# BSPD.net
KiCad netlist of a schematic drawn in Altium Designer
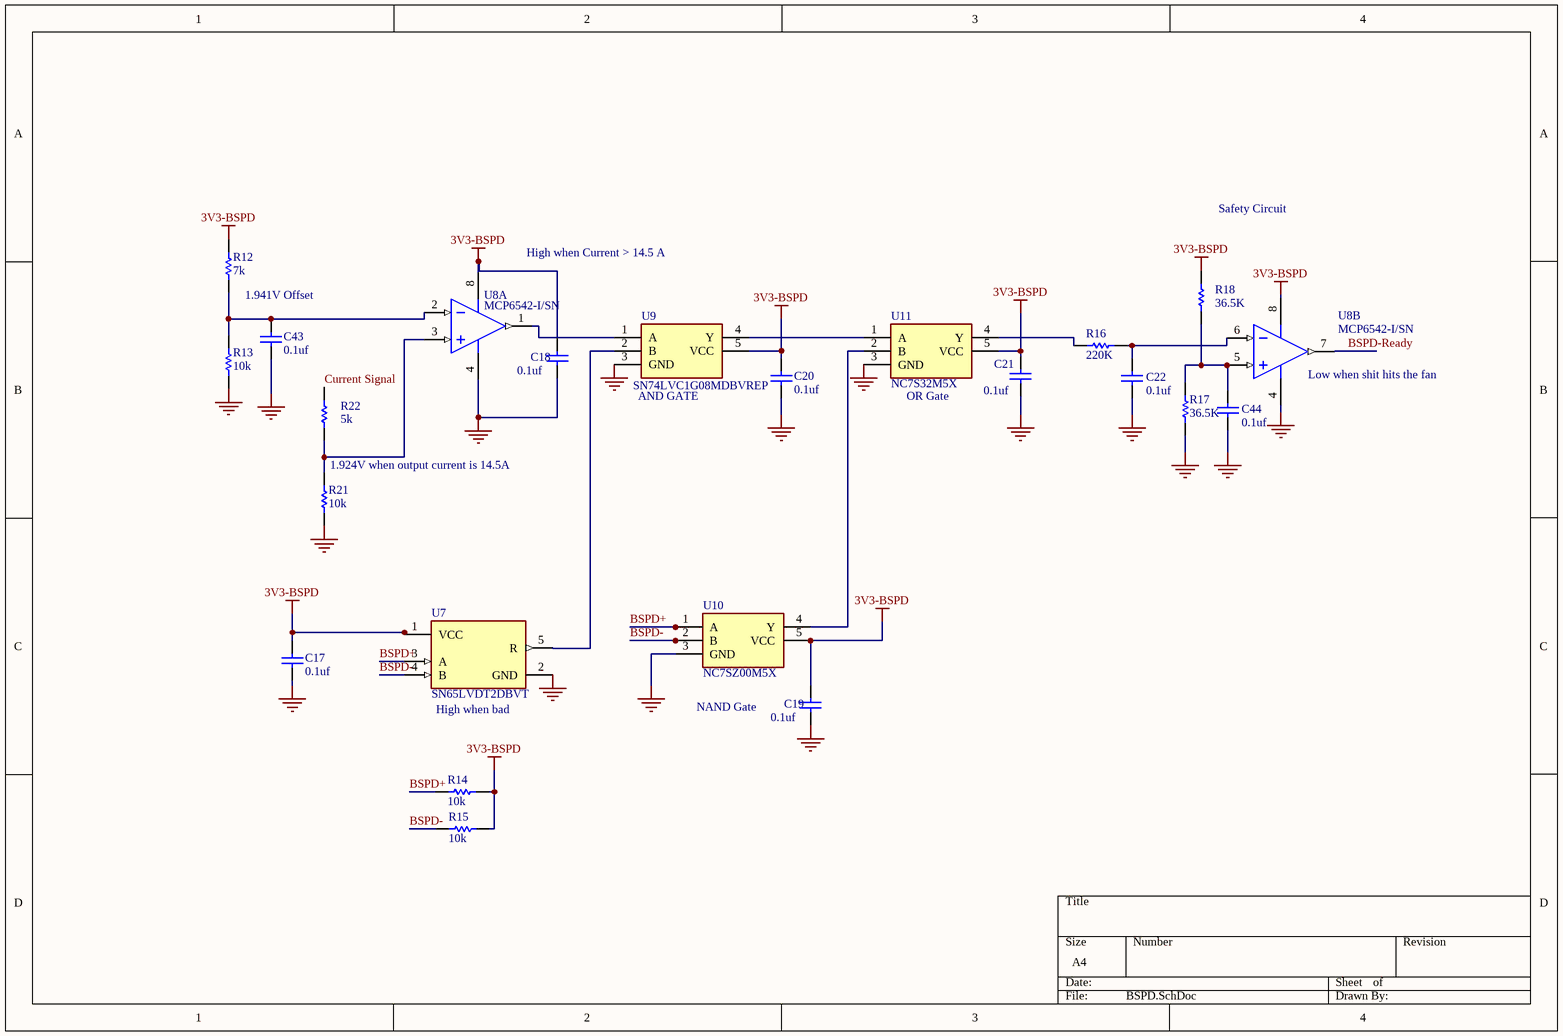
[diagram p0: BSPD.SchDoc]

(export (version "E")
  (design (tool "Eeschema 10.0.6"))
  (components
    (comp (ref "C17")
      (value "0.1uf")
      (footprint "CAPC1608X95N")
      (description "264-4630")
      (fields (field (name "Comment") "Cap") (field (name "PUBLISHER") "Altium Limited"))
      (libsource (lib "Miscellaneous Devices") (part "Cap"))
    )
    (comp (ref "C18")
      (value "0.1uf")
      (footprint "CAPC1608X95N")
      (description "264-4630")
      (fields (field (name "Comment") "Cap") (field (name "PUBLISHER") "Altium Limited"))
      (libsource (lib "Miscellaneous Devices") (part "Cap"))
    )
    (comp (ref "C19")
      (value "0.1uf")
      (footprint "CAPC1608X95N")
      (description "264-4630")
      (fields (field (name "Comment") "Cap") (field (name "PUBLISHER") "Altium Limited"))
      (libsource (lib "Miscellaneous Devices") (part "Cap"))
    )
    (comp (ref "C20")
      (value "0.1uf")
      (footprint "CAPC1608X95N")
      (description "264-4630")
      (fields (field (name "Comment") "Cap") (field (name "PUBLISHER") "Altium Limited"))
      (libsource (lib "Miscellaneous Devices") (part "Cap"))
    )
    (comp (ref "C21")
      (value "0.1uf")
      (footprint "CAPC1608X95N")
      (description "264-4630")
      (fields (field (name "Comment") "Cap") (field (name "PUBLISHER") "Altium Limited"))
      (libsource (lib "Miscellaneous Devices") (part "Cap"))
    )
    (comp (ref "C22")
      (value "0.1uf")
      (footprint "CAPC1608X95N")
      (description "264-4630")
      (fields (field (name "Comment") "Cap") (field (name "PUBLISHER") "Altium Limited"))
      (libsource (lib "Miscellaneous Devices") (part "Cap"))
    )
    (comp (ref "C43")
      (value "0.1uf")
      (footprint "CAPC1608X95N")
      (description "264-4630")
      (fields (field (name "Comment") "Cap") (field (name "PUBLISHER") "Altium Limited"))
      (libsource (lib "Miscellaneous Devices") (part "Cap"))
    )
    (comp (ref "C44")
      (value "0.1uf")
      (footprint "CAPC1608X95N")
      (description "264-4630")
      (fields (field (name "Comment") "Cap") (field (name "PUBLISHER") "Altium Limited"))
      (libsource (lib "Miscellaneous Devices") (part "Cap"))
    )
    (comp (ref "R12")
      (value "7k")
      (footprint "RESC1608X55N")
      (description "CRCW06033K24FKEA")
      (fields (field (name "Comment") "Res1") (field (name "PUBLISHER") "Altium Limited"))
      (libsource (lib "Miscellaneous Devices") (part "Res1"))
    )
    (comp (ref "R13")
      (value "10k")
      (footprint "RESC1608X55N")
      (description "169-4216")
      (fields (field (name "Comment") "Res1") (field (name "PUBLISHER") "Altium Limited"))
      (libsource (lib "Miscellaneous Devices") (part "Res1"))
    )
    (comp (ref "R14")
      (value "10k")
      (footprint "RESC1608X55N")
      (description "169-4216")
      (fields (field (name "Comment") "Res1") (field (name "PUBLISHER") "Altium Limited"))
      (libsource (lib "Miscellaneous Devices") (part "Res1"))
    )
    (comp (ref "R15")
      (value "10k")
      (footprint "RESC1608X55N")
      (description "169-4216")
      (fields (field (name "Comment") "Res1") (field (name "PUBLISHER") "Altium Limited"))
      (libsource (lib "Miscellaneous Devices") (part "Res1"))
    )
    (comp (ref "R16")
      (value "220K")
      (footprint "RESC1608X55N")
      (description "120-842")
      (fields (field (name "Comment") "Res1") (field (name "PUBLISHER") "Altium Limited"))
      (libsource (lib "Miscellaneous Devices") (part "Res1"))
    )
    (comp (ref "R17")
      (value "36.5K")
      (footprint "RESC1608X55N")
      (description "169-4216")
      (fields (field (name "Comment") "Res1") (field (name "PUBLISHER") "Altium Limited"))
      (libsource (lib "Miscellaneous Devices") (part "Res1"))
    )
    (comp (ref "R18")
      (value "36.5K")
      (footprint "RESC1608X55N")
      (description "679-0260")
      (fields (field (name "Comment") "Res1") (field (name "PUBLISHER") "Altium Limited"))
      (libsource (lib "Miscellaneous Devices") (part "Res1"))
    )
    (comp (ref "R21")
      (value "10k")
      (footprint "RESC1608X55N")
      (description "169-4216")
      (fields (field (name "Comment") "Res1") (field (name "PUBLISHER") "Altium Limited"))
      (libsource (lib "Miscellaneous Devices") (part "Res1"))
    )
    (comp (ref "R22")
      (value "5k")
      (footprint "RESC1608X55N")
      (description "CRCW06033K24FKEA")
      (fields (field (name "Comment") "Res1") (field (name "PUBLISHER") "Altium Limited"))
      (libsource (lib "Miscellaneous Devices") (part "Res1"))
    )
    (comp (ref "U7")
      (value "SN65LVDT2DBVT")
      (footprint "FP-DBV0005A-MFG")
      (description "IC RECEIVER 0/1 SOT23-5")
      (fields
        (field (name "OCTOPART") "https://octopart.com/sn65lvdt2dbvt-texas+instruments-712102")
        (field (name "MANUFACTURER") "Texas Instruments")
      )
      (libsource (lib "Altium Content Vault") (part "80154aa7be0093f96882e9a6708b811"))
    )
    (comp (ref "U8")
      (value "MCP6542-I/SN")
      (footprint "SOIC-SN8_N")
      (description "Push-Pull Output Sub-Microamp Comparator, 8-Pin SOIC, Industrial Temperature")
      (libsource (lib "Altium Content Vault") (part "LO-COMP-MCP6542-IL8"))
    )
    (comp (ref "U9")
      (value "SN74LVC1G08MDBVREP")
      (footprint "SamacSys:SOT95P280X145-5N")
      (description "Integrated Circuit")
      (fields (field (name "MOUSER2 PART NUMBER") "595-SN74LVC08MDBVREP"))
      (libsource (lib "*") (part "SN74LVC1G08MDBVREP"))
    )
    (comp (ref "U10")
      (value "NC7SZ00M5X")
      (footprint "SOT95P280X125-5N")
      (description "NAND GATEEE")
      (fields (field (name "MANUFACTURER_PART_NUMBER") "NC7S02M5X"))
      (libsource (lib "SamacSys") (part "NC7S02M5X"))
    )
    (comp (ref "U11")
      (value "NC7S32M5X")
      (footprint "SOT95P275X110-5N")
      (description "OR GATEEEE")
      (libsource (lib "SamacSys") (part "NC7S32M5X"))
    )
  )
  (nets
    (net (code "1") (name "/BSPD+") (class "Default")
      (node (ref "R14") (pin "1") (pinfunction "1_1") (pintype "passive"))
      (node (ref "U10") (pin "1") (pinfunction "A_1") (pintype "passive"))
      (node (ref "U7") (pin "3") (pinfunction "A_3") (pintype "input"))
    )
    (net (code "2") (name "/BSPD-") (class "Default")
      (node (ref "R15") (pin "1") (pinfunction "1_1") (pintype "passive"))
      (node (ref "U10") (pin "2") (pinfunction "B_2") (pintype "passive"))
      (node (ref "U7") (pin "4") (pinfunction "B_4") (pintype "input"))
    )
    (net (code "3") (name "/BSPD-Ready") (class "Default")
      (node (ref "U8") (pin "7") (pinfunction "OUTB_7") (pintype "output"))
    )
    (net (code "4") (name "/Current Signal") (class "Default")
      (node (ref "R22") (pin "2") (pinfunction "2_2") (pintype "passive"))
    )
    (net (code "5") (name "3V3-BSPD") (class "Default")
      (node (ref "C17") (pin "2") (pinfunction "2_2") (pintype "passive"))
      (node (ref "C18") (pin "2") (pinfunction "2_2") (pintype "passive"))
      (node (ref "C19") (pin "2") (pinfunction "2_2") (pintype "passive"))
      (node (ref "C20") (pin "2") (pinfunction "2_2") (pintype "passive"))
      (node (ref "C21") (pin "2") (pinfunction "2_2") (pintype "passive"))
      (node (ref "R12") (pin "2") (pinfunction "2_2") (pintype "passive"))
      (node (ref "R14") (pin "2") (pinfunction "2_2") (pintype "passive"))
      (node (ref "R15") (pin "2") (pinfunction "2_2") (pintype "passive"))
      (node (ref "R18") (pin "2") (pinfunction "2_2") (pintype "passive"))
      (node (ref "U10") (pin "5") (pinfunction "VCC_5") (pintype "passive"))
      (node (ref "U11") (pin "5") (pinfunction "VCC_5") (pintype "passive"))
      (node (ref "U7") (pin "1") (pinfunction "VCC_1") (pintype "power_in"))
      (node (ref "U8") (pin "8") (pinfunction "VDD_8") (pintype "power_in"))
      (node (ref "U9") (pin "5") (pinfunction "VCC_5") (pintype "passive"))
    )
    (net (code "6") (name "GND") (class "Default")
      (node (ref "C17") (pin "1") (pinfunction "1_1") (pintype "passive"))
      (node (ref "C18") (pin "1") (pinfunction "1_1") (pintype "passive"))
      (node (ref "C19") (pin "1") (pinfunction "1_1") (pintype "passive"))
      (node (ref "C20") (pin "1") (pinfunction "1_1") (pintype "passive"))
      (node (ref "C21") (pin "1") (pinfunction "1_1") (pintype "passive"))
      (node (ref "C22") (pin "1") (pinfunction "1_1") (pintype "passive"))
      (node (ref "C43") (pin "1") (pinfunction "1_1") (pintype "passive"))
      (node (ref "C44") (pin "1") (pinfunction "1_1") (pintype "passive"))
      (node (ref "R13") (pin "1") (pinfunction "1_1") (pintype "passive"))
      (node (ref "R17") (pin "1") (pinfunction "1_1") (pintype "passive"))
      (node (ref "R21") (pin "1") (pinfunction "1_1") (pintype "passive"))
      (node (ref "U10") (pin "3") (pinfunction "GND_3") (pintype "passive"))
      (node (ref "U11") (pin "3") (pinfunction "GND_3") (pintype "passive"))
      (node (ref "U7") (pin "2") (pinfunction "GND_2") (pintype "power_in"))
      (node (ref "U8") (pin "4") (pinfunction "VSS_4") (pintype "power_in"))
      (node (ref "U9") (pin "3") (pinfunction "GND_3") (pintype "passive"))
    )
    (net (code "7") (name "Net-(U7-R)") (class "Default")
      (node (ref "U7") (pin "5") (pinfunction "R_5") (pintype "output"))
      (node (ref "U9") (pin "2") (pinfunction "B_2") (pintype "passive"))
    )
    (net (code "8") (name "Net-(U8A-OUTA)") (class "Default")
      (node (ref "U8") (pin "1") (pinfunction "OUTA_1") (pintype "output"))
      (node (ref "U9") (pin "1") (pinfunction "A_1") (pintype "passive"))
    )
    (net (code "9") (name "Net-(U8A-VINA+)") (class "Default")
      (node (ref "R21") (pin "2") (pinfunction "2_2") (pintype "passive"))
      (node (ref "R22") (pin "1") (pinfunction "1_1") (pintype "passive"))
      (node (ref "U8") (pin "3") (pinfunction "VINA+_3") (pintype "input"))
    )
    (net (code "10") (name "Net-(U8A-VINA-)") (class "Default")
      (node (ref "C43") (pin "2") (pinfunction "2_2") (pintype "passive"))
      (node (ref "R12") (pin "1") (pinfunction "1_1") (pintype "passive"))
      (node (ref "R13") (pin "2") (pinfunction "2_2") (pintype "passive"))
      (node (ref "U8") (pin "2") (pinfunction "VINA-_2") (pintype "input"))
    )
    (net (code "11") (name "Net-(U8B-VINB+)") (class "Default")
      (node (ref "C44") (pin "2") (pinfunction "2_2") (pintype "passive"))
      (node (ref "R17") (pin "2") (pinfunction "2_2") (pintype "passive"))
      (node (ref "R18") (pin "1") (pinfunction "1_1") (pintype "passive"))
      (node (ref "U8") (pin "5") (pinfunction "VINB+_5") (pintype "input"))
    )
    (net (code "12") (name "Net-(U8B-VINB-)") (class "Default")
      (node (ref "C22") (pin "2") (pinfunction "2_2") (pintype "passive"))
      (node (ref "R16") (pin "1") (pinfunction "1_1") (pintype "passive"))
      (node (ref "U8") (pin "6") (pinfunction "VINB-_6") (pintype "input"))
    )
    (net (code "13") (name "Net-(U10-Y)") (class "Default")
      (node (ref "U10") (pin "4") (pinfunction "Y_4") (pintype "passive"))
      (node (ref "U11") (pin "2") (pinfunction "B_2") (pintype "passive"))
    )
    (net (code "14") (name "Net-(U11-A)") (class "Default")
      (node (ref "U11") (pin "1") (pinfunction "A_1") (pintype "passive"))
      (node (ref "U9") (pin "4") (pinfunction "Y_4") (pintype "passive"))
    )
    (net (code "15") (name "Net-(U11-Y)") (class "Default")
      (node (ref "R16") (pin "2") (pinfunction "2_2") (pintype "passive"))
      (node (ref "U11") (pin "4") (pinfunction "Y_4") (pintype "passive"))
    )
  )
)
